# Buksir.net
KiCad netlist of a schematic drawn in EAGLE
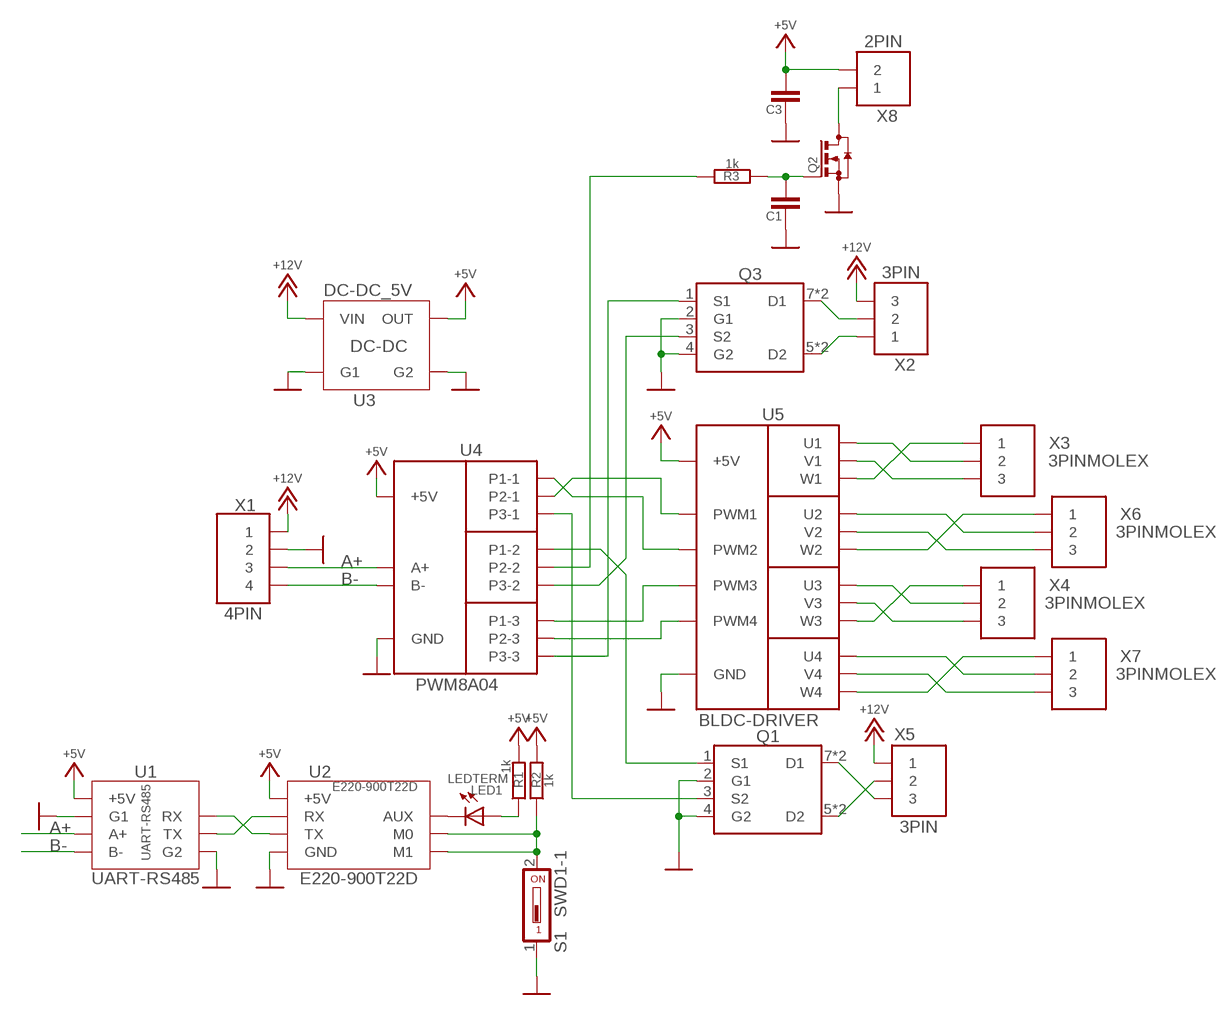
[diagram p0: schematic, sheet 1]

(export (version "E")
  (design (tool "Eeschema 10.0.6"))
  (components
    (comp (ref "C1")
      (value "CAPACITOR1206")
      (footprint "eagle-import:C1206")
      (libsource (lib "eagle-import") (part "CAPACITOR1206"))
    )
    (comp (ref "C3")
      (value "CAPACITOR1206")
      (footprint "eagle-import:C1206")
      (libsource (lib "eagle-import") (part "CAPACITOR1206"))
    )
    (comp (ref "LED1")
      (value "LEDTERM")
      (footprint "eagle-import:LED_TERM")
      (libsource (lib "eagle-import") (part "LEDTERM"))
    )
    (comp (ref "Q1")
      (value "NCV8402ADDR2G")
      (footprint "eagle-import:SOIC-8")
      (libsource (lib "eagle-import") (part "NCV8402ADDR2G"))
    )
    (comp (ref "Q2")
      (value "FET-N")
      (footprint "eagle-import:SOT23")
      (libsource (lib "eagle-import") (part "FET-N"))
    )
    (comp (ref "Q3")
      (value "NCV8402ADDR2G")
      (footprint "eagle-import:SOIC-8")
      (libsource (lib "eagle-import") (part "NCV8402ADDR2G"))
    )
    (comp (ref "R1")
      (value "1k")
      (footprint "eagle-import:R0805")
      (libsource (lib "eagle-import") (part "RESISTOR0805"))
    )
    (comp (ref "R2")
      (value "1k")
      (footprint "eagle-import:R0805")
      (libsource (lib "eagle-import") (part "RESISTOR0805"))
    )
    (comp (ref "R3")
      (value "1k")
      (footprint "eagle-import:R0805")
      (libsource (lib "eagle-import") (part "RESISTOR0805"))
    )
    (comp (ref "S1")
      (value "SWD1-1")
      (footprint "eagle-import:DS-01")
      (libsource (lib "eagle-import") (part "DS01"))
    )
    (comp (ref "U1")
      (value "UART-RS485")
      (footprint "eagle-import:UART-RS485")
      (libsource (lib "eagle-import") (part "UART-RS485"))
    )
    (comp (ref "U2")
      (value "E220-900T22D")
      (footprint "eagle-import:E220-900T22D")
      (libsource (lib "eagle-import") (part "E220-900T22D"))
    )
    (comp (ref "U3")
      (value "DC-DC_5V")
      (footprint "eagle-import:DC-DC_5V")
      (libsource (lib "eagle-import") (part "DC-DC_5V"))
    )
    (comp (ref "U4")
      (value "PWM8A04")
      (footprint "eagle-import:PWM8A04")
      (libsource (lib "eagle-import") (part "PWM8A04"))
    )
    (comp (ref "U5")
      (value "BLDC-DRIVER")
      (footprint "eagle-import:BLDC-DRIVER")
      (libsource (lib "eagle-import") (part "BLDC-DRIVER"))
    )
    (comp (ref "X1")
      (value "4PIN")
      (footprint "eagle-import:4PIN-2.5MM")
      (libsource (lib "eagle-import") (part "4PIN"))
    )
    (comp (ref "X2")
      (value "3PIN")
      (footprint "eagle-import:3PIN-2.5MM")
      (libsource (lib "eagle-import") (part "3PIN"))
    )
    (comp (ref "X3")
      (value "3PINMOLEX")
      (footprint "eagle-import:3PIN-MOLEX")
      (libsource (lib "eagle-import") (part "3PINMOLEX"))
    )
    (comp (ref "X4")
      (value "3PINMOLEX")
      (footprint "eagle-import:3PIN-MOLEX")
      (libsource (lib "eagle-import") (part "3PINMOLEX"))
    )
    (comp (ref "X5")
      (value "3PIN")
      (footprint "eagle-import:3PIN-2.5MM")
      (libsource (lib "eagle-import") (part "3PIN"))
    )
    (comp (ref "X6")
      (value "3PINMOLEX")
      (footprint "eagle-import:3PIN-MOLEX")
      (libsource (lib "eagle-import") (part "3PINMOLEX"))
    )
    (comp (ref "X7")
      (value "3PINMOLEX")
      (footprint "eagle-import:3PIN-MOLEX")
      (libsource (lib "eagle-import") (part "3PINMOLEX"))
    )
    (comp (ref "X8")
      (value "2PIN")
      (footprint "eagle-import:2PIN-2.5MM")
      (libsource (lib "eagle-import") (part "2PIN"))
    )
  )
  (nets
    (net (code "1") (name "+5V") (class "Default")
      (node (ref "C3") (pin "2") (pinfunction "2_2") (pintype "passive"))
      (node (ref "R1") (pin "2") (pinfunction "2_2") (pintype "passive"))
      (node (ref "R2") (pin "2") (pinfunction "2_2") (pintype "passive"))
      (node (ref "U1") (pin "VCC") (pinfunction "+5V_VCC") (pintype "bidirectional"))
      (node (ref "U2") (pin "VCC") (pinfunction "+5V_VCC") (pintype "bidirectional"))
      (node (ref "U3") (pin "OUT") (pinfunction "OUT_OUT") (pintype "bidirectional"))
      (node (ref "U4") (pin "+V") (pinfunction "+5V_+V") (pintype "bidirectional"))
      (node (ref "U5") (pin "B+") (pinfunction "+5V_B+") (pintype "bidirectional"))
      (node (ref "X8") (pin "P$2") (pinfunction "2_P$2") (pintype "bidirectional"))
    )
    (net (code "2") (name "+12V") (class "Default")
      (node (ref "U3") (pin "VIN") (pinfunction "VIN_VIN") (pintype "bidirectional"))
      (node (ref "X1") (pin "P$4") (pinfunction "1_P$4") (pintype "bidirectional"))
      (node (ref "X2") (pin "P$3") (pinfunction "3_P$3") (pintype "bidirectional"))
      (node (ref "X5") (pin "P$1") (pinfunction "1_P$1") (pintype "bidirectional"))
    )
    (net (code "3") (name "/A+") (class "Default")
      (node (ref "U1") (pin "A+") (pinfunction "A+_A+") (pintype "bidirectional"))
      (node (ref "U4") (pin "A+") (pinfunction "A+_A+") (pintype "bidirectional"))
      (node (ref "X1") (pin "P$2") (pinfunction "3_P$2") (pintype "bidirectional"))
    )
    (net (code "4") (name "/B-") (class "Default")
      (node (ref "U1") (pin "B-") (pinfunction "B-_B-") (pintype "bidirectional"))
      (node (ref "U4") (pin "B-") (pinfunction "B-_B-") (pintype "bidirectional"))
      (node (ref "X1") (pin "P$1") (pinfunction "4_P$1") (pintype "bidirectional"))
    )
    (net (code "5") (name "GND") (class "Default")
      (node (ref "C1") (pin "1") (pinfunction "1_1") (pintype "passive"))
      (node (ref "C3") (pin "1") (pinfunction "1_1") (pintype "passive"))
      (node (ref "Q1") (pin "2") (pinfunction "G1_2") (pintype "input"))
      (node (ref "Q1") (pin "4") (pinfunction "G2_4") (pintype "input"))
      (node (ref "Q2") (pin "2") (pinfunction "S_2") (pintype "passive"))
      (node (ref "Q3") (pin "2") (pinfunction "G1_2") (pintype "input"))
      (node (ref "Q3") (pin "4") (pinfunction "G2_4") (pintype "input"))
      (node (ref "S1") (pin "1") (pinfunction "1_1") (pintype "passive"))
      (node (ref "U1") (pin "G1") (pinfunction "G1_G1") (pintype "bidirectional"))
      (node (ref "U1") (pin "G2") (pinfunction "G2_G2") (pintype "bidirectional"))
      (node (ref "U2") (pin "GND") (pinfunction "GND_GND") (pintype "bidirectional"))
      (node (ref "U3") (pin "G1") (pinfunction "G1_G1") (pintype "bidirectional"))
      (node (ref "U3") (pin "G2") (pinfunction "G2_G2") (pintype "bidirectional"))
      (node (ref "U4") (pin "GND") (pinfunction "GND_GND") (pintype "bidirectional"))
      (node (ref "U5") (pin "B-") (pinfunction "GND_B-") (pintype "bidirectional"))
      (node (ref "X1") (pin "P$3") (pinfunction "2_P$3") (pintype "bidirectional"))
    )
    (net (code "6") (name "Net-(LED1-C)") (class "Default")
      (node (ref "LED1") (pin "K") (pinfunction "C_K") (pintype "passive"))
      (node (ref "U2") (pin "AUX") (pinfunction "AUX_AUX") (pintype "bidirectional"))
    )
    (net (code "7") (name "Net-(LED1-PadA)") (class "Default")
      (node (ref "LED1") (pin "A") (pinfunction "A_A") (pintype "passive"))
      (node (ref "R1") (pin "1") (pinfunction "1_1") (pintype "passive"))
    )
    (net (code "8") (name "Net-(Q1-S1)") (class "Default")
      (node (ref "Q1") (pin "1") (pinfunction "S1_1") (pintype "power_in"))
      (node (ref "U4") (pin "P1-2") (pinfunction "P1-2_P1-2") (pintype "bidirectional"))
    )
    (net (code "9") (name "Net-(Q1-S2)") (class "Default")
      (node (ref "Q1") (pin "3") (pinfunction "S2_3") (pintype "power_in"))
      (node (ref "U4") (pin "P3-1") (pinfunction "P3-1_P3-1") (pintype "bidirectional"))
    )
    (net (code "10") (name "Net-(Q2-D)") (class "Default")
      (node (ref "Q2") (pin "3") (pinfunction "D_3") (pintype "passive"))
      (node (ref "X8") (pin "P$1") (pinfunction "1_P$1") (pintype "bidirectional"))
    )
    (net (code "11") (name "Net-(Q2-G)") (class "Default")
      (node (ref "C1") (pin "2") (pinfunction "2_2") (pintype "passive"))
      (node (ref "Q2") (pin "1") (pinfunction "G_1") (pintype "passive"))
      (node (ref "R3") (pin "1") (pinfunction "1_1") (pintype "passive"))
    )
    (net (code "12") (name "Net-(Q3-S1)") (class "Default")
      (node (ref "Q3") (pin "1") (pinfunction "S1_1") (pintype "power_in"))
      (node (ref "U4") (pin "P3-3") (pinfunction "P3-3_P3-3") (pintype "bidirectional"))
    )
    (net (code "13") (name "Net-(Q3-S2)") (class "Default")
      (node (ref "Q3") (pin "3") (pinfunction "S2_3") (pintype "power_in"))
      (node (ref "U4") (pin "P3-2") (pinfunction "P3-2_P3-2") (pintype "bidirectional"))
    )
    (net (code "14") (name "Net-(R2-Pad1)") (class "Default")
      (node (ref "R2") (pin "1") (pinfunction "1_1") (pintype "passive"))
      (node (ref "S1") (pin "2") (pinfunction "2_2") (pintype "passive"))
      (node (ref "U2") (pin "M0") (pinfunction "M0_M0") (pintype "bidirectional"))
      (node (ref "U2") (pin "M1") (pinfunction "M1_M1") (pintype "bidirectional"))
    )
    (net (code "15") (name "Net-(R3-Pad2)") (class "Default")
      (node (ref "R3") (pin "2") (pinfunction "2_2") (pintype "passive"))
      (node (ref "U4") (pin "P2-2") (pinfunction "P2-2_P2-2") (pintype "bidirectional"))
    )
    (net (code "16") (name "Net-(U2-RX)") (class "Default")
      (node (ref "U1") (pin "TX") (pinfunction "TX_TX") (pintype "bidirectional"))
      (node (ref "U2") (pin "RXD") (pinfunction "RX_RXD") (pintype "bidirectional"))
    )
    (net (code "17") (name "Net-(U2-TX)") (class "Default")
      (node (ref "U1") (pin "RX") (pinfunction "RX_RX") (pintype "bidirectional"))
      (node (ref "U2") (pin "TXD") (pinfunction "TX_TXD") (pintype "bidirectional"))
    )
    (net (code "18") (name "Net-(U4-PadP1-1)") (class "Default")
      (node (ref "U4") (pin "P1-1") (pinfunction "P1-1_P1-1") (pintype "bidirectional"))
      (node (ref "U5") (pin "PWM2") (pinfunction "PWM2_PWM2") (pintype "bidirectional"))
    )
    (net (code "19") (name "Net-(U4-PadP1-3)") (class "Default")
      (node (ref "U4") (pin "P1-3") (pinfunction "P1-3_P1-3") (pintype "bidirectional"))
      (node (ref "U5") (pin "PWM3") (pinfunction "PWM3_PWM3") (pintype "bidirectional"))
    )
    (net (code "20") (name "Net-(U4-PadP2-1)") (class "Default")
      (node (ref "U4") (pin "P2-1") (pinfunction "P2-1_P2-1") (pintype "bidirectional"))
      (node (ref "U5") (pin "PWM1") (pinfunction "PWM1_PWM1") (pintype "bidirectional"))
    )
    (net (code "21") (name "Net-(U4-PadP2-3)") (class "Default")
      (node (ref "U4") (pin "P2-3") (pinfunction "P2-3_P2-3") (pintype "bidirectional"))
      (node (ref "U5") (pin "PWM4") (pinfunction "PWM4_PWM4") (pintype "bidirectional"))
    )
    (net (code "22") (name "Net-(X2-1)") (class "Default")
      (node (ref "Q3") (pin "5") (pinfunction "D2_5") (pintype "output"))
      (node (ref "Q3") (pin "6") (pinfunction "D2_6") (pintype "output"))
      (node (ref "X2") (pin "P$1") (pinfunction "1_P$1") (pintype "bidirectional"))
    )
    (net (code "23") (name "Net-(X2-2)") (class "Default")
      (node (ref "Q3") (pin "7") (pinfunction "D1_7") (pintype "output"))
      (node (ref "Q3") (pin "8") (pinfunction "D1_8") (pintype "output"))
      (node (ref "X2") (pin "P$2") (pinfunction "2_P$2") (pintype "bidirectional"))
    )
    (net (code "24") (name "Net-(X3-1)") (class "Default")
      (node (ref "U5") (pin "W1") (pinfunction "W1_W1") (pintype "bidirectional"))
      (node (ref "X3") (pin "P$1") (pinfunction "1_P$1") (pintype "bidirectional"))
    )
    (net (code "25") (name "Net-(X3-2)") (class "Default")
      (node (ref "U5") (pin "U1") (pinfunction "U1_U1") (pintype "bidirectional"))
      (node (ref "X3") (pin "P$2") (pinfunction "2_P$2") (pintype "bidirectional"))
    )
    (net (code "26") (name "Net-(X3-3)") (class "Default")
      (node (ref "U5") (pin "V1") (pinfunction "V1_V1") (pintype "bidirectional"))
      (node (ref "X3") (pin "P$3") (pinfunction "3_P$3") (pintype "bidirectional"))
    )
    (net (code "27") (name "Net-(X4-1)") (class "Default")
      (node (ref "U5") (pin "W3") (pinfunction "W3_W3") (pintype "bidirectional"))
      (node (ref "X4") (pin "P$1") (pinfunction "1_P$1") (pintype "bidirectional"))
    )
    (net (code "28") (name "Net-(X4-2)") (class "Default")
      (node (ref "U5") (pin "U3") (pinfunction "U3_U3") (pintype "bidirectional"))
      (node (ref "X4") (pin "P$2") (pinfunction "2_P$2") (pintype "bidirectional"))
    )
    (net (code "29") (name "Net-(X4-3)") (class "Default")
      (node (ref "U5") (pin "V3") (pinfunction "V3_V3") (pintype "bidirectional"))
      (node (ref "X4") (pin "P$3") (pinfunction "3_P$3") (pintype "bidirectional"))
    )
    (net (code "30") (name "Net-(X5-2)") (class "Default")
      (node (ref "Q1") (pin "5") (pinfunction "D2_5") (pintype "output"))
      (node (ref "Q1") (pin "6") (pinfunction "D2_6") (pintype "output"))
      (node (ref "X5") (pin "P$2") (pinfunction "2_P$2") (pintype "bidirectional"))
    )
    (net (code "31") (name "Net-(X5-3)") (class "Default")
      (node (ref "Q1") (pin "7") (pinfunction "D1_7") (pintype "output"))
      (node (ref "Q1") (pin "8") (pinfunction "D1_8") (pintype "output"))
      (node (ref "X5") (pin "P$3") (pinfunction "3_P$3") (pintype "bidirectional"))
    )
    (net (code "32") (name "Net-(X6-1)") (class "Default")
      (node (ref "U5") (pin "W2") (pinfunction "W2_W2") (pintype "bidirectional"))
      (node (ref "X6") (pin "P$1") (pinfunction "1_P$1") (pintype "bidirectional"))
    )
    (net (code "33") (name "Net-(X6-2)") (class "Default")
      (node (ref "U5") (pin "U2") (pinfunction "U2_U2") (pintype "bidirectional"))
      (node (ref "X6") (pin "P$2") (pinfunction "2_P$2") (pintype "bidirectional"))
    )
    (net (code "34") (name "Net-(X6-3)") (class "Default")
      (node (ref "U5") (pin "V2") (pinfunction "V2_V2") (pintype "bidirectional"))
      (node (ref "X6") (pin "P$3") (pinfunction "3_P$3") (pintype "bidirectional"))
    )
    (net (code "35") (name "Net-(X7-1)") (class "Default")
      (node (ref "U5") (pin "W4") (pinfunction "W4_W4") (pintype "bidirectional"))
      (node (ref "X7") (pin "P$1") (pinfunction "1_P$1") (pintype "bidirectional"))
    )
    (net (code "36") (name "Net-(X7-2)") (class "Default")
      (node (ref "U5") (pin "U4") (pinfunction "U4_U4") (pintype "bidirectional"))
      (node (ref "X7") (pin "P$2") (pinfunction "2_P$2") (pintype "bidirectional"))
    )
    (net (code "37") (name "Net-(X7-3)") (class "Default")
      (node (ref "U5") (pin "V4") (pinfunction "V4_V4") (pintype "bidirectional"))
      (node (ref "X7") (pin "P$3") (pinfunction "3_P$3") (pintype "bidirectional"))
    )
  )
)
